# ng_H___Led_7_Thanh__Duy_b_nh_quy.net
KiCad netlist of a schematic drawn in Altium Designer
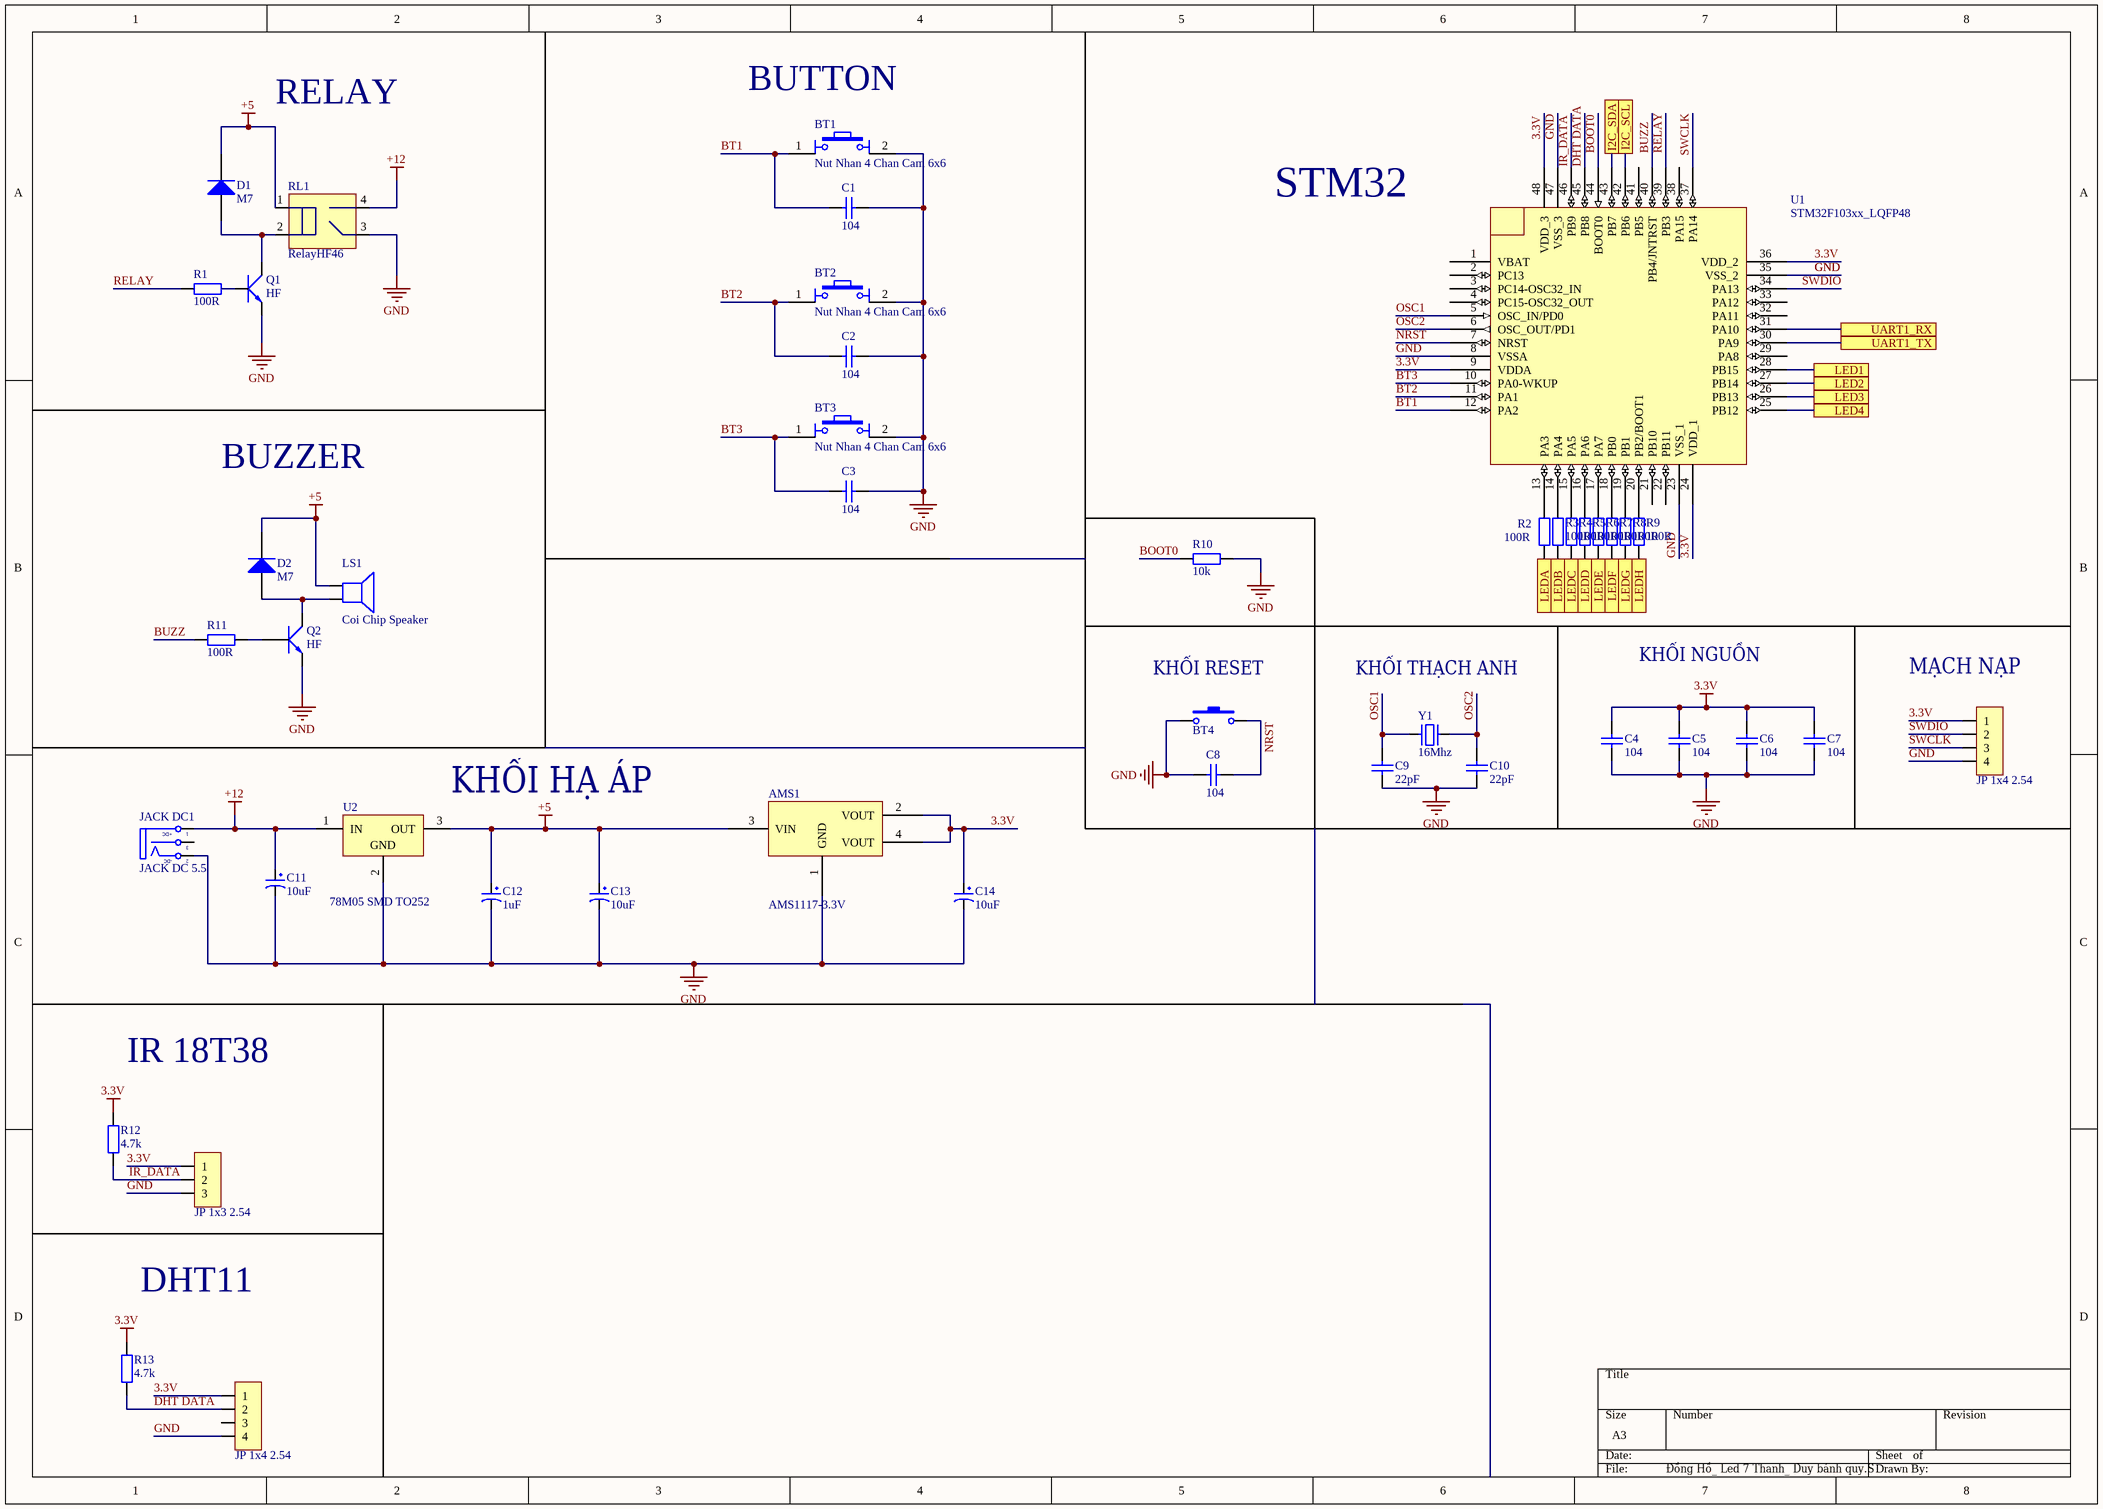
[diagram p0: Đồng Hồ_ Led 7 Thanh_ Duy bánh quy.SchDoc]

(export (version "E")
  (design (tool "Eeschema 10.0.6"))
  (components
    (comp (ref "AMS1")
      (value "AMS1117-3.3V")
      (footprint "SOT223")
      (description "Dán")
      (libsource (lib "Altium_Lib_by_KhueNguyenCreator") (part "AMS1117 SMD"))
    )
    (comp (ref "BT1")
      (value "Nut Nhan 4 Chan Cam 6x6")
      (footprint "Nut Nhan 4 Chan Cam 6x6")
      (description "Nut Nhan 4 Chan 6x6mm")
      (libsource (lib "Altium_Lib_by_KhueNguyenCreator") (part "Nut Nhan 4 Chan Cam 6x6"))
    )
    (comp (ref "BT2")
      (value "Nut Nhan 4 Chan Cam 6x6")
      (footprint "Nut Nhan 4 Chan Cam 6x6")
      (description "Nut Nhan 4 Chan 6x6mm")
      (libsource (lib "Altium_Lib_by_KhueNguyenCreator") (part "Nut Nhan 4 Chan Cam 6x6"))
    )
    (comp (ref "BT3")
      (value "Nut Nhan 4 Chan Cam 6x6")
      (footprint "Nut Nhan 4 Chan Cam 6x6")
      (description "Nut Nhan 4 Chan 6x6mm")
      (libsource (lib "Altium_Lib_by_KhueNguyenCreator") (part "Nut Nhan 4 Chan Cam 6x6"))
    )
    (comp (ref "BT4")
      (value "Nut Nhan 2 Chan SMD 3x6x2.5")
      (footprint "Nut Nhan 2 Chan SMD 3x6x2.5")
      (libsource (lib "Altium_Lib_by_KhueNguyenCreator") (part "Nut Nhan 2 Chan SMD 3x6x2.5"))
    )
    (comp (ref "C1")
      (value "104")
      (footprint "tu 0805")
      (description "Dán")
      (libsource (lib "Altium_Lib_by_KhueNguyenCreator") (part "Tu 0805 104 50V 10%"))
    )
    (comp (ref "C2")
      (value "104")
      (footprint "tu 0805")
      (description "Dán")
      (libsource (lib "Altium_Lib_by_KhueNguyenCreator") (part "Tu 0805 104 50V 10%"))
    )
    (comp (ref "C3")
      (value "104")
      (footprint "tu 0805")
      (description "Dán")
      (libsource (lib "Altium_Lib_by_KhueNguyenCreator") (part "Tu 0805 104 50V 10%"))
    )
    (comp (ref "C4")
      (value "104")
      (footprint "tu 0805")
      (description "Dán")
      (libsource (lib "Altium_Lib_by_KhueNguyenCreator") (part "Tu 0805 104 50V 10%"))
    )
    (comp (ref "C5")
      (value "104")
      (footprint "tu 0805")
      (description "Dán")
      (libsource (lib "Altium_Lib_by_KhueNguyenCreator") (part "Tu 0805 104 50V 10%"))
    )
    (comp (ref "C6")
      (value "104")
      (footprint "tu 0805")
      (description "Dán")
      (libsource (lib "Altium_Lib_by_KhueNguyenCreator") (part "Tu 0805 104 50V 10%"))
    )
    (comp (ref "C7")
      (value "104")
      (footprint "tu 0805")
      (description "Dán")
      (libsource (lib "Altium_Lib_by_KhueNguyenCreator") (part "Tu 0805 104 50V 10%"))
    )
    (comp (ref "C8")
      (value "104")
      (footprint "tu 0805")
      (description "Dán")
      (libsource (lib "Altium_Lib_by_KhueNguyenCreator") (part "Tu 0805 104 50V 10%"))
    )
    (comp (ref "C9")
      (value "22pF")
      (footprint "tu 0805")
      (description "Dán")
      (libsource (lib "Altium_Lib_by_KhueNguyenCreator") (part "Tu 0805 22pF 50V 10%"))
    )
    (comp (ref "C10")
      (value "22pF")
      (footprint "tu 0805")
      (description "Dán")
      (libsource (lib "Altium_Lib_by_KhueNguyenCreator") (part "Tu 0805 22pF 50V 10%"))
    )
    (comp (ref "C11")
      (value "10uF")
      (footprint "tu tantalum smd3216")
      (description "Dán")
      (libsource (lib "Altium_Lib_by_KhueNguyenCreator") (part "Tu tantalum 10uF 16V SMD3216"))
    )
    (comp (ref "C12")
      (value "1uF")
      (footprint "tu tantalum smd3216")
      (description "Dán")
      (libsource (lib "Altium_Lib_by_KhueNguyenCreator") (part "Tu tantalum 1uF 35V SMD3216"))
    )
    (comp (ref "C13")
      (value "10uF")
      (footprint "tu tantalum smd3216")
      (description "Dán")
      (libsource (lib "Altium_Lib_by_KhueNguyenCreator") (part "Tu tantalum 10uF 16V SMD3216"))
    )
    (comp (ref "C14")
      (value "10uF")
      (footprint "tu tantalum smd3216")
      (description "Dán")
      (libsource (lib "Altium_Lib_by_KhueNguyenCreator") (part "Tu tantalum 10uF 16V SMD3216"))
    )
    (comp (ref "D1")
      (value "M7")
      (footprint "DIODE SMA")
      (description "Dán")
      (libsource (lib "Altium_Lib_by_KhueNguyenCreator") (part "Diode M7 ( 4007 )"))
    )
    (comp (ref "D2")
      (value "M7")
      (footprint "DIODE SMA")
      (description "Dán")
      (libsource (lib "Altium_Lib_by_KhueNguyenCreator") (part "Diode M7 ( 4007 )"))
    )
    (comp (ref "JACK DC1")
      (value "JACK DC 5.5")
      (footprint "JACK DC 5.5")
      (libsource (lib "Altium_Lib_by_KhueNguyenCreator") (part "JACK DC 5.5"))
    )
    (comp (ref "JP1")
      (value "JP 1x4 2.54")
      (footprint "JP 1x4 DC")
      (description "Cắm")
      (libsource (lib "Altium_Lib_by_KhueNguyenCreator") (part "JP 1x4 2.54 Duc Cong"))
    )
    (comp (ref "JP2")
      (value "JP 1x3 2.54")
      (footprint "JP 1x3 CT")
      (description "Cắm")
      (libsource (lib "Altium_Lib_by_KhueNguyenCreator") (part "JP 1x3 2.54 Cai Thang"))
    )
    (comp (ref "JP3")
      (value "JP 1x4 2.54")
      (footprint "JP 1x4 CT")
      (description "Cắm")
      (libsource (lib "Altium_Lib_by_KhueNguyenCreator") (part "JP 1x4 2.54 Cai Thang"))
    )
    (comp (ref "LS1")
      (value "Coi Chip Speaker")
      (footprint "Coi Chip Speacker")
      (description "Còi chip")
      (libsource (lib "Altium_Lib_by_KhueNguyenCreator") (part "Coi Chip Speaker"))
    )
    (comp (ref "Q1")
      (value "HF")
      (footprint "SOT23")
      (description "NPN transistor")
      (libsource (lib "Altium_Lib_by_KhueNguyenCreator") (part "C1815 HF SMD"))
    )
    (comp (ref "Q2")
      (value "HF")
      (footprint "SOT23")
      (description "NPN transistor")
      (libsource (lib "Altium_Lib_by_KhueNguyenCreator") (part "C1815 HF SMD"))
    )
    (comp (ref "R1")
      (value "100R")
      (footprint "tro smd 0603")
      (description "Dán")
      (libsource (lib "Altium_Lib_by_KhueNguyenCreator") (part "Tro 0603 5% 100R"))
    )
    (comp (ref "R2")
      (value "100R")
      (footprint "tro smd 0603")
      (description "Dán")
      (libsource (lib "Altium_Lib_by_KhueNguyenCreator") (part "Tro 0603 5% 100R"))
    )
    (comp (ref "R3")
      (value "100R")
      (footprint "tro smd 0603")
      (description "Dán")
      (libsource (lib "Altium_Lib_by_KhueNguyenCreator") (part "Tro 0603 5% 100R"))
    )
    (comp (ref "R4")
      (value "100R")
      (footprint "tro smd 0603")
      (description "Dán")
      (libsource (lib "Altium_Lib_by_KhueNguyenCreator") (part "Tro 0603 5% 100R"))
    )
    (comp (ref "R5")
      (value "100R")
      (footprint "tro smd 0603")
      (description "Dán")
      (libsource (lib "Altium_Lib_by_KhueNguyenCreator") (part "Tro 0603 5% 100R"))
    )
    (comp (ref "R6")
      (value "100R")
      (footprint "tro smd 0603")
      (description "Dán")
      (libsource (lib "Altium_Lib_by_KhueNguyenCreator") (part "Tro 0603 5% 100R"))
    )
    (comp (ref "R7")
      (value "100R")
      (footprint "tro smd 0603")
      (description "Dán")
      (libsource (lib "Altium_Lib_by_KhueNguyenCreator") (part "Tro 0603 5% 100R"))
    )
    (comp (ref "R8")
      (value "100R")
      (footprint "tro smd 0603")
      (description "Dán")
      (libsource (lib "Altium_Lib_by_KhueNguyenCreator") (part "Tro 0603 5% 100R"))
    )
    (comp (ref "R9")
      (value "100R")
      (footprint "tro smd 0603")
      (description "Dán")
      (libsource (lib "Altium_Lib_by_KhueNguyenCreator") (part "Tro 0603 5% 100R"))
    )
    (comp (ref "R10")
      (value "10k")
      (footprint "tro smd 0603")
      (description "Dán")
      (libsource (lib "Altium_Lib_by_KhueNguyenCreator") (part "Tro 0603 1% 10k"))
    )
    (comp (ref "R11")
      (value "100R")
      (footprint "tro smd 0603")
      (description "Dán")
      (libsource (lib "Altium_Lib_by_KhueNguyenCreator") (part "Tro 0603 5% 100R"))
    )
    (comp (ref "R12")
      (value "4.7k")
      (footprint "tro smd 0805")
      (description "Dán")
      (libsource (lib "Altium_Lib_by_KhueNguyenCreator") (part "Tro 0805 5% 4.7k"))
    )
    (comp (ref "R13")
      (value "4.7k")
      (footprint "tro smd 0805")
      (description "Dán")
      (libsource (lib "Altium_Lib_by_KhueNguyenCreator") (part "Tro 0805 5% 4.7k"))
    )
    (comp (ref "RL1")
      (value "RelayHF46")
      (footprint "Relay 4 chan HF46F")
      (description "Relay 4 chan HF46F")
      (libsource (lib "Altium_Lib_by_KhueNguyenCreator") (part "Relay 4 chan HF46F"))
    )
    (comp (ref "U1")
      (value "STM32F103xx_LQFP48")
      (footprint "STM32_LQPF48")
      (fields (field (name "PUBLISHER") "Altium Limited"))
      (libsource (lib "Altium_Lib_by_KhueNguyenCreator") (part "STM32F103xx_LQFP48"))
    )
    (comp (ref "U2")
      (value "78M05 SMD TO252")
      (footprint "TO252")
      (description "Dán")
      (libsource (lib "Altium_Lib_by_KhueNguyenCreator") (part "78M05 SMD TO252"))
    )
    (comp (ref "Y1")
      (value "16Mhz")
      (footprint "Thach Anh 2 chan SMD")
      (description "Crystal For all Crystal 2pin.")
      (libsource (lib "Altium_Lib_by_KhueNguyenCreator") (part "Thach Anh 2 chan SMD"))
    )
  )
  (nets
    (net (code "1") (name "+5") (class "Default")
      (node (ref "AMS1") (pin "3") (pinfunction "VIN_3") (pintype "passive"))
      (node (ref "C12") (pin "1") (pinfunction "1_1") (pintype "passive"))
      (node (ref "C13") (pin "1") (pinfunction "1_1") (pintype "passive"))
      (node (ref "D1") (pin "2") (pinfunction "K_2") (pintype "passive"))
      (node (ref "D2") (pin "2") (pinfunction "K_2") (pintype "passive"))
      (node (ref "LS1") (pin "1") (pinfunction "1_1") (pintype "passive"))
      (node (ref "RL1") (pin "1") (pintype "passive"))
      (node (ref "U2") (pin "3") (pinfunction "OUT_3") (pintype "power_in"))
    )
    (net (code "2") (name "+12") (class "Default")
      (node (ref "C11") (pin "1") (pinfunction "1_1") (pintype "passive"))
      (node (ref "JACK DC1") (pin "1") (pinfunction "T_1") (pintype "passive"))
      (node (ref "RL1") (pin "4") (pinfunction "AC/DC_4") (pintype "passive"))
      (node (ref "U2") (pin "1") (pinfunction "IN_1") (pintype "power_in"))
    )
    (net (code "3") (name "/BOOT0") (class "Default")
      (node (ref "R10") (pin "1") (pinfunction "1_1") (pintype "passive"))
      (node (ref "U1") (pin "44") (pinfunction "BOOT0_44") (pintype "input"))
    )
    (net (code "4") (name "/BT1") (class "Default")
      (node (ref "BT1") (pin "1") (pintype "passive"))
      (node (ref "C1") (pin "2") (pinfunction "2_2") (pintype "passive"))
      (node (ref "U1") (pin "12") (pinfunction "PA2_12") (pintype "bidirectional"))
    )
    (net (code "5") (name "/BT2") (class "Default")
      (node (ref "BT2") (pin "1") (pintype "passive"))
      (node (ref "C2") (pin "2") (pinfunction "2_2") (pintype "passive"))
      (node (ref "U1") (pin "11") (pinfunction "PA1_11") (pintype "bidirectional"))
    )
    (net (code "6") (name "/BT3") (class "Default")
      (node (ref "BT3") (pin "1") (pintype "passive"))
      (node (ref "C3") (pin "2") (pinfunction "2_2") (pintype "passive"))
      (node (ref "U1") (pin "10") (pinfunction "PA0-WKUP_10") (pintype "bidirectional"))
    )
    (net (code "7") (name "/BUZZ") (class "Default")
      (node (ref "R11") (pin "1") (pinfunction "1_1") (pintype "passive"))
      (node (ref "U1") (pin "40") (pinfunction "PB4/JNTRST_40") (pintype "bidirectional"))
    )
    (net (code "8") (name "/DHT DATA") (class "Default")
      (node (ref "JP3") (pin "2") (pinfunction "2_2") (pintype "passive"))
      (node (ref "R13") (pin "1") (pinfunction "1_1") (pintype "passive"))
      (node (ref "U1") (pin "45") (pinfunction "PB8_45") (pintype "bidirectional"))
    )
    (net (code "9") (name "/I2C_SCL") (class "Default")
      (node (ref "U1") (pin "42") (pinfunction "PB6_42") (pintype "bidirectional"))
    )
    (net (code "10") (name "/I2C_SDA") (class "Default")
      (node (ref "U1") (pin "43") (pinfunction "PB7_43") (pintype "bidirectional"))
    )
    (net (code "11") (name "/IR_DATA") (class "Default")
      (node (ref "JP2") (pin "2") (pinfunction "2_2") (pintype "passive"))
      (node (ref "R12") (pin "1") (pinfunction "1_1") (pintype "passive"))
      (node (ref "U1") (pin "46") (pinfunction "PB9_46") (pintype "bidirectional"))
    )
    (net (code "12") (name "/LED1") (class "Default")
      (node (ref "U1") (pin "28") (pinfunction "PB15_28") (pintype "bidirectional"))
    )
    (net (code "13") (name "/LED2") (class "Default")
      (node (ref "U1") (pin "27") (pinfunction "PB14_27") (pintype "bidirectional"))
    )
    (net (code "14") (name "/LED3") (class "Default")
      (node (ref "U1") (pin "26") (pinfunction "PB13_26") (pintype "bidirectional"))
    )
    (net (code "15") (name "/LED4") (class "Default")
      (node (ref "U1") (pin "25") (pinfunction "PB12_25") (pintype "bidirectional"))
    )
    (net (code "16") (name "/LEDA") (class "Default")
      (node (ref "R2") (pin "1") (pinfunction "1_1") (pintype "passive"))
    )
    (net (code "17") (name "/LEDB") (class "Default")
      (node (ref "R3") (pin "1") (pinfunction "1_1") (pintype "passive"))
    )
    (net (code "18") (name "/LEDC") (class "Default")
      (node (ref "R4") (pin "1") (pinfunction "1_1") (pintype "passive"))
    )
    (net (code "19") (name "/LEDD") (class "Default")
      (node (ref "R5") (pin "1") (pinfunction "1_1") (pintype "passive"))
    )
    (net (code "20") (name "/LEDE") (class "Default")
      (node (ref "R6") (pin "1") (pinfunction "1_1") (pintype "passive"))
    )
    (net (code "21") (name "/LEDF") (class "Default")
      (node (ref "R7") (pin "1") (pinfunction "1_1") (pintype "passive"))
    )
    (net (code "22") (name "/LEDG") (class "Default")
      (node (ref "R8") (pin "1") (pinfunction "1_1") (pintype "passive"))
    )
    (net (code "23") (name "/LEDH") (class "Default")
      (node (ref "R9") (pin "1") (pinfunction "1_1") (pintype "passive"))
    )
    (net (code "24") (name "/NRST") (class "Default")
      (node (ref "BT4") (pin "2") (pinfunction "2_2") (pintype "passive"))
      (node (ref "C8") (pin "1") (pinfunction "1_1") (pintype "passive"))
      (node (ref "U1") (pin "7") (pinfunction "NRST_7") (pintype "bidirectional"))
    )
    (net (code "25") (name "/OSC1") (class "Default")
      (node (ref "C9") (pin "2") (pinfunction "2_2") (pintype "passive"))
      (node (ref "U1") (pin "5") (pinfunction "OSC_IN/PD0_5") (pintype "input"))
      (node (ref "Y1") (pin "1") (pinfunction "1_1") (pintype "passive"))
    )
    (net (code "26") (name "/OSC2") (class "Default")
      (node (ref "C10") (pin "2") (pinfunction "2_2") (pintype "passive"))
      (node (ref "U1") (pin "6") (pinfunction "OSC_OUT/PD1_6") (pintype "output"))
      (node (ref "Y1") (pin "2") (pinfunction "2_2") (pintype "passive"))
    )
    (net (code "27") (name "/RELAY") (class "Default")
      (node (ref "R1") (pin "1") (pinfunction "1_1") (pintype "passive"))
      (node (ref "U1") (pin "39") (pinfunction "PB3_39") (pintype "bidirectional"))
    )
    (net (code "28") (name "/SWCLK") (class "Default")
      (node (ref "JP1") (pin "3") (pinfunction "3_3") (pintype "passive"))
      (node (ref "U1") (pin "37") (pinfunction "PA14_37") (pintype "bidirectional"))
    )
    (net (code "29") (name "/SWDIO") (class "Default")
      (node (ref "JP1") (pin "2") (pinfunction "2_2") (pintype "passive"))
      (node (ref "U1") (pin "34") (pinfunction "PA13_34") (pintype "bidirectional"))
    )
    (net (code "30") (name "/UART1_RX") (class "Default")
      (node (ref "U1") (pin "31") (pinfunction "PA10_31") (pintype "bidirectional"))
    )
    (net (code "31") (name "/UART1_TX") (class "Default")
      (node (ref "U1") (pin "30") (pinfunction "PA9_30") (pintype "bidirectional"))
    )
    (net (code "32") (name "3.3V") (class "Default")
      (node (ref "AMS1") (pin "2") (pinfunction "VOUT_2") (pintype "passive"))
      (node (ref "AMS1") (pin "4") (pinfunction "VOUT_4") (pintype "passive"))
      (node (ref "C14") (pin "1") (pinfunction "1_1") (pintype "passive"))
      (node (ref "C4") (pin "1") (pinfunction "1_1") (pintype "passive"))
      (node (ref "C5") (pin "1") (pinfunction "1_1") (pintype "passive"))
      (node (ref "C6") (pin "1") (pinfunction "1_1") (pintype "passive"))
      (node (ref "C7") (pin "1") (pinfunction "1_1") (pintype "passive"))
      (node (ref "JP1") (pin "1") (pinfunction "1_1") (pintype "passive"))
      (node (ref "JP2") (pin "1") (pinfunction "1_1") (pintype "passive"))
      (node (ref "JP3") (pin "1") (pinfunction "1_1") (pintype "passive"))
      (node (ref "R12") (pin "2") (pinfunction "2_2") (pintype "passive"))
      (node (ref "R13") (pin "2") (pinfunction "2_2") (pintype "passive"))
      (node (ref "U1") (pin "24") (pinfunction "VDD_1_24") (pintype "power_in"))
      (node (ref "U1") (pin "36") (pinfunction "VDD_2_36") (pintype "power_in"))
      (node (ref "U1") (pin "48") (pinfunction "VDD_3_48") (pintype "power_in"))
      (node (ref "U1") (pin "9") (pinfunction "VDDA_9") (pintype "power_in"))
    )
    (net (code "33") (name "GND") (class "Default")
      (node (ref "AMS1") (pin "1") (pinfunction "GND_1") (pintype "passive"))
      (node (ref "BT1") (pin "2") (pintype "passive"))
      (node (ref "BT2") (pin "2") (pintype "passive"))
      (node (ref "BT3") (pin "2") (pintype "passive"))
      (node (ref "BT4") (pin "1") (pinfunction "1_1") (pintype "passive"))
      (node (ref "C1") (pin "1") (pinfunction "1_1") (pintype "passive"))
      (node (ref "C10") (pin "1") (pinfunction "1_1") (pintype "passive"))
      (node (ref "C11") (pin "2") (pinfunction "2_2") (pintype "passive"))
      (node (ref "C12") (pin "2") (pinfunction "2_2") (pintype "passive"))
      (node (ref "C13") (pin "2") (pinfunction "2_2") (pintype "passive"))
      (node (ref "C14") (pin "2") (pinfunction "2_2") (pintype "passive"))
      (node (ref "C2") (pin "1") (pinfunction "1_1") (pintype "passive"))
      (node (ref "C3") (pin "1") (pinfunction "1_1") (pintype "passive"))
      (node (ref "C4") (pin "2") (pinfunction "2_2") (pintype "passive"))
      (node (ref "C5") (pin "2") (pinfunction "2_2") (pintype "passive"))
      (node (ref "C6") (pin "2") (pinfunction "2_2") (pintype "passive"))
      (node (ref "C7") (pin "2") (pinfunction "2_2") (pintype "passive"))
      (node (ref "C8") (pin "2") (pinfunction "2_2") (pintype "passive"))
      (node (ref "C9") (pin "1") (pinfunction "1_1") (pintype "passive"))
      (node (ref "JACK DC1") (pin "2") (pinfunction "TN_2") (pintype "passive"))
      (node (ref "JP1") (pin "4") (pinfunction "4_4") (pintype "passive"))
      (node (ref "JP2") (pin "3") (pinfunction "3_3") (pintype "passive"))
      (node (ref "JP3") (pin "4") (pinfunction "4_4") (pintype "passive"))
      (node (ref "Q1") (pin "2") (pinfunction "E_2") (pintype "passive"))
      (node (ref "Q2") (pin "2") (pinfunction "E_2") (pintype "passive"))
      (node (ref "R10") (pin "2") (pinfunction "2_2") (pintype "passive"))
      (node (ref "RL1") (pin "3") (pinfunction "AC/DC_3") (pintype "passive"))
      (node (ref "U1") (pin "23") (pinfunction "VSS_1_23") (pintype "power_in"))
      (node (ref "U1") (pin "35") (pinfunction "VSS_2_35") (pintype "power_in"))
      (node (ref "U1") (pin "47") (pinfunction "VSS_3_47") (pintype "power_in"))
      (node (ref "U1") (pin "8") (pinfunction "VSSA_8") (pintype "power_in"))
      (node (ref "U2") (pin "2") (pinfunction "GND_2") (pintype "power_in"))
    )
    (net (code "34") (name "Net-(D1-A)") (class "Default")
      (node (ref "D1") (pin "1") (pinfunction "A_1") (pintype "passive"))
      (node (ref "Q1") (pin "3") (pinfunction "C_3") (pintype "passive"))
      (node (ref "RL1") (pin "2") (pintype "passive"))
    )
    (net (code "35") (name "Net-(D2-A)") (class "Default")
      (node (ref "D2") (pin "1") (pinfunction "A_1") (pintype "passive"))
      (node (ref "LS1") (pin "2") (pinfunction "2_2") (pintype "passive"))
      (node (ref "Q2") (pin "3") (pinfunction "C_3") (pintype "passive"))
    )
    (net (code "36") (name "Net-(Q1-B)") (class "Default")
      (node (ref "Q1") (pin "1") (pinfunction "B_1") (pintype "passive"))
      (node (ref "R1") (pin "2") (pinfunction "2_2") (pintype "passive"))
    )
    (net (code "37") (name "Net-(Q2-B)") (class "Default")
      (node (ref "Q2") (pin "1") (pinfunction "B_1") (pintype "passive"))
      (node (ref "R11") (pin "2") (pinfunction "2_2") (pintype "passive"))
    )
    (net (code "38") (name "Net-(U1-PA3)") (class "Default")
      (node (ref "R2") (pin "2") (pinfunction "2_2") (pintype "passive"))
      (node (ref "U1") (pin "13") (pinfunction "PA3_13") (pintype "bidirectional"))
    )
    (net (code "39") (name "Net-(U1-PA4)") (class "Default")
      (node (ref "R3") (pin "2") (pinfunction "2_2") (pintype "passive"))
      (node (ref "U1") (pin "14") (pinfunction "PA4_14") (pintype "bidirectional"))
    )
    (net (code "40") (name "Net-(U1-PA5)") (class "Default")
      (node (ref "R4") (pin "2") (pinfunction "2_2") (pintype "passive"))
      (node (ref "U1") (pin "15") (pinfunction "PA5_15") (pintype "bidirectional"))
    )
    (net (code "41") (name "Net-(U1-PA6)") (class "Default")
      (node (ref "R5") (pin "2") (pinfunction "2_2") (pintype "passive"))
      (node (ref "U1") (pin "16") (pinfunction "PA6_16") (pintype "bidirectional"))
    )
    (net (code "42") (name "Net-(U1-PA7)") (class "Default")
      (node (ref "R6") (pin "2") (pinfunction "2_2") (pintype "passive"))
      (node (ref "U1") (pin "17") (pinfunction "PA7_17") (pintype "bidirectional"))
    )
    (net (code "43") (name "Net-(U1-PB0)") (class "Default")
      (node (ref "R7") (pin "2") (pinfunction "2_2") (pintype "passive"))
      (node (ref "U1") (pin "18") (pinfunction "PB0_18") (pintype "bidirectional"))
    )
    (net (code "44") (name "Net-(U1-PB1)") (class "Default")
      (node (ref "R8") (pin "2") (pinfunction "2_2") (pintype "passive"))
      (node (ref "U1") (pin "19") (pinfunction "PB1_19") (pintype "bidirectional"))
    )
    (net (code "45") (name "Net-(U1-PB2{slash}BOOT1)") (class "Default")
      (node (ref "R9") (pin "2") (pinfunction "2_2") (pintype "passive"))
      (node (ref "U1") (pin "20") (pinfunction "PB2/BOOT1_20") (pintype "bidirectional"))
    )
    (net (code "46") (name "unconnected-(JACK DC1-S-Pad3)") (class "Default")
      (node (ref "JACK DC1") (pin "3") (pinfunction "S_3") (pintype "power_in"))
    )
    (net (code "47") (name "unconnected-(JP3-Pad3)") (class "Default")
      (node (ref "JP3") (pin "3") (pinfunction "3_3") (pintype "passive"))
    )
    (net (code "48") (name "unconnected-(U1-PA8-Pad29)") (class "Default")
      (node (ref "U1") (pin "29") (pinfunction "PA8_29") (pintype "bidirectional"))
    )
    (net (code "49") (name "unconnected-(U1-PA11-Pad32)") (class "Default")
      (node (ref "U1") (pin "32") (pinfunction "PA11_32") (pintype "bidirectional"))
    )
    (net (code "50") (name "unconnected-(U1-PA12-Pad33)") (class "Default")
      (node (ref "U1") (pin "33") (pinfunction "PA12_33") (pintype "bidirectional"))
    )
    (net (code "51") (name "unconnected-(U1-PA15-Pad38)") (class "Default")
      (node (ref "U1") (pin "38") (pinfunction "PA15_38") (pintype "bidirectional"))
    )
    (net (code "52") (name "unconnected-(U1-PB5-Pad41)") (class "Default")
      (node (ref "U1") (pin "41") (pinfunction "PB5_41") (pintype "bidirectional"))
    )
    (net (code "53") (name "unconnected-(U1-PB10-Pad21)") (class "Default")
      (node (ref "U1") (pin "21") (pinfunction "PB10_21") (pintype "bidirectional"))
    )
    (net (code "54") (name "unconnected-(U1-PB11-Pad22)") (class "Default")
      (node (ref "U1") (pin "22") (pinfunction "PB11_22") (pintype "bidirectional"))
    )
    (net (code "55") (name "unconnected-(U1-PC13-Pad2)") (class "Default")
      (node (ref "U1") (pin "2") (pinfunction "PC13_2") (pintype "bidirectional"))
    )
    (net (code "56") (name "unconnected-(U1-PC14-OSC32_IN-Pad3)") (class "Default")
      (node (ref "U1") (pin "3") (pinfunction "PC14-OSC32_IN_3") (pintype "bidirectional"))
    )
    (net (code "57") (name "unconnected-(U1-PC15-OSC32_OUT-Pad4)") (class "Default")
      (node (ref "U1") (pin "4") (pinfunction "PC15-OSC32_OUT_4") (pintype "bidirectional"))
    )
    (net (code "58") (name "unconnected-(U1-VBAT-Pad1)") (class "Default")
      (node (ref "U1") (pin "1") (pinfunction "VBAT_1") (pintype "power_in"))
    )
  )
)
